# PDB2.net
KiCad netlist of a schematic drawn in EAGLE
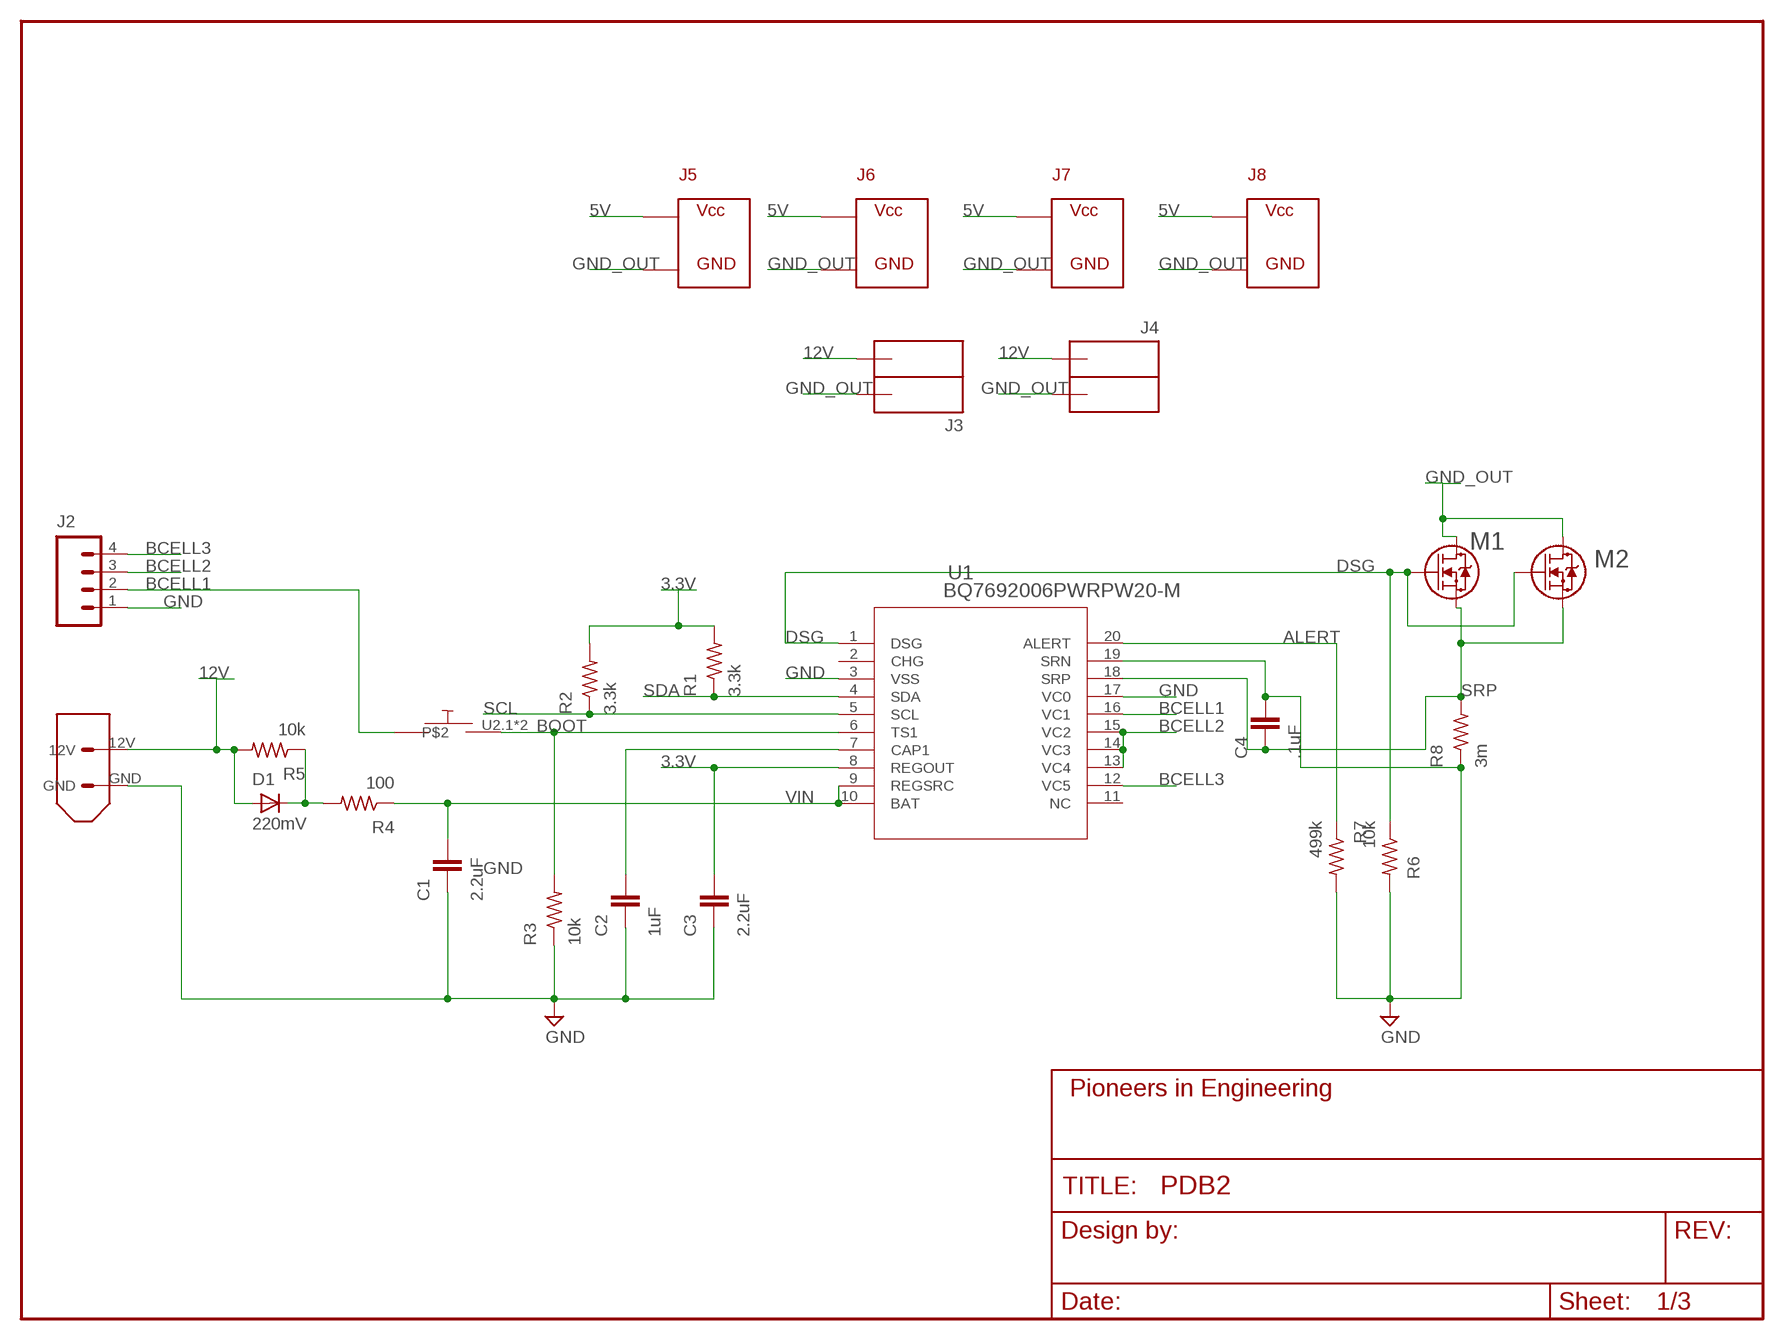
[diagram p0: schematic, sheet 1]
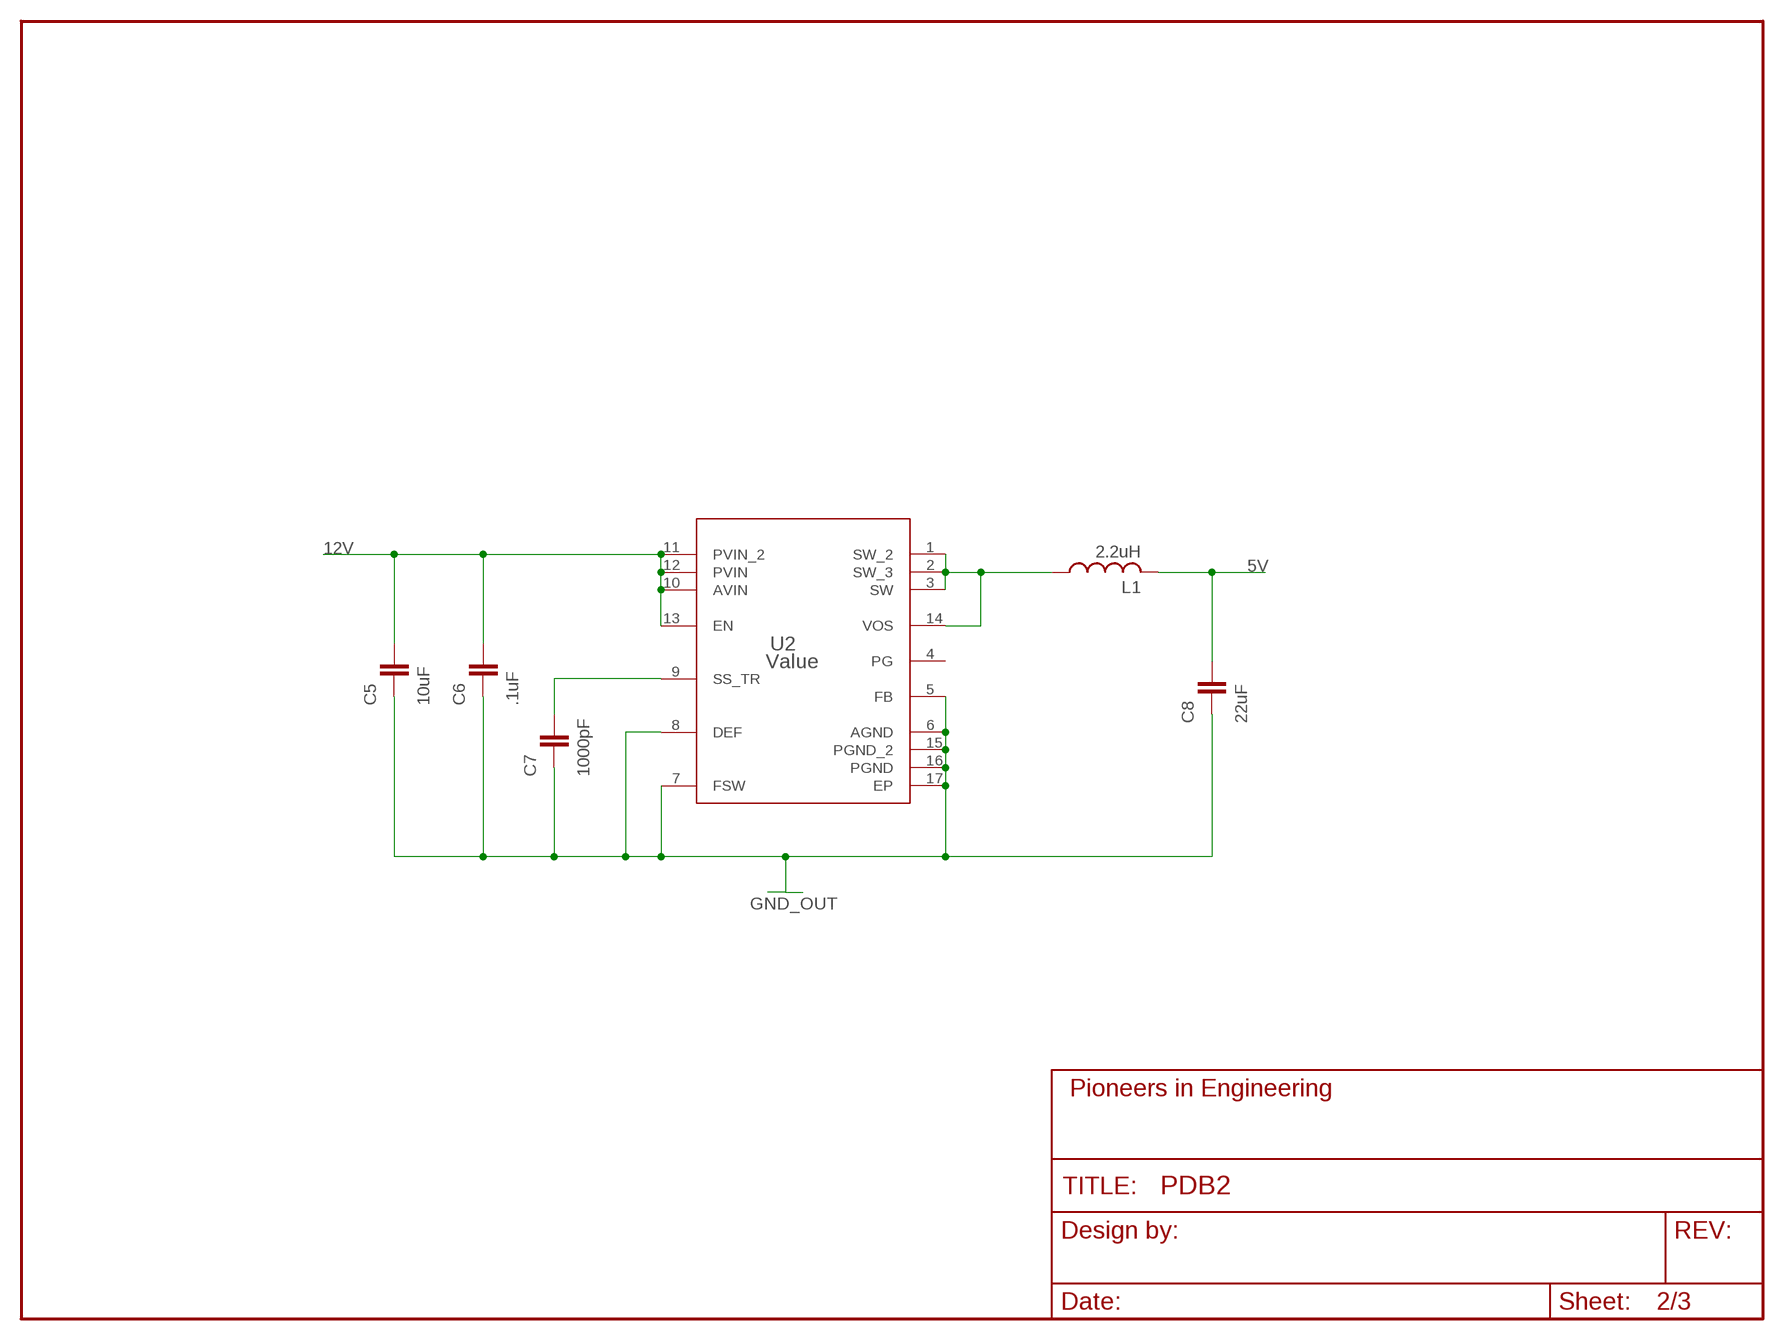
[diagram p1: schematic, sheet 2]
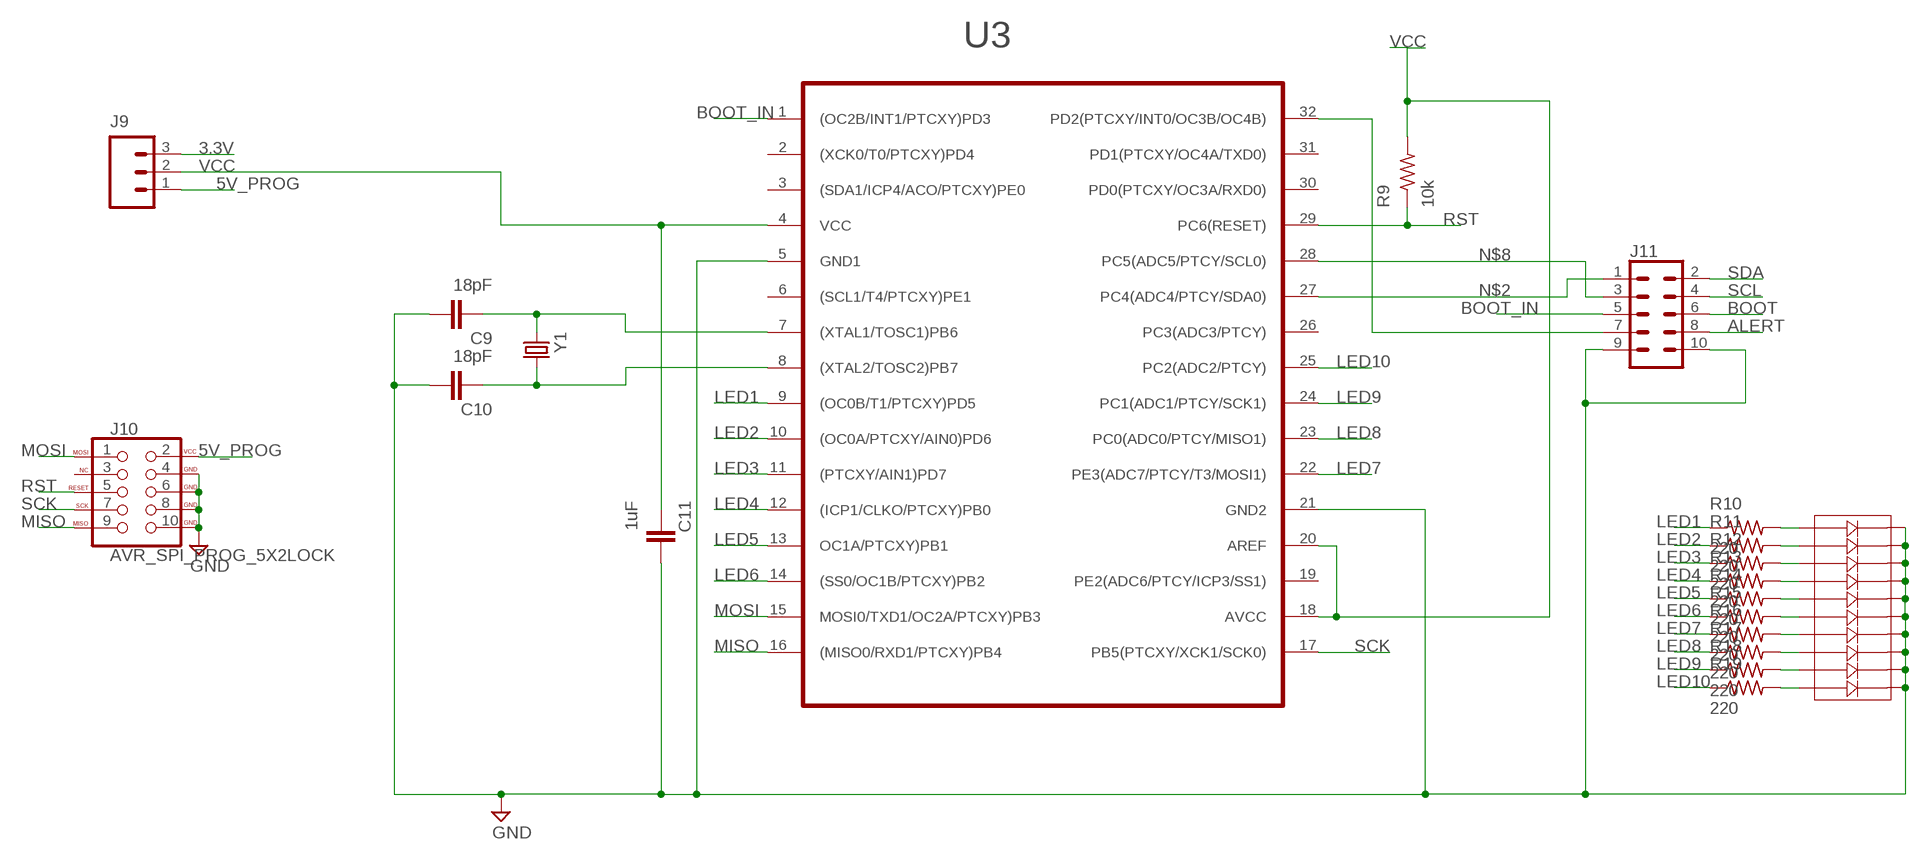
[diagram p2: schematic, sheet 3]

(export (version "E")
  (design (tool "Eeschema 10.0.6"))
  (components
    (comp (ref "C9")
      (value "18pF")
      (footprint "eagle-import:0603-CAP")
      (libsource (lib "eagle-import") (part "CAP0603-CAP"))
    )
    (comp (ref "C10")
      (value "18pF")
      (footprint "eagle-import:0603-CAP")
      (libsource (lib "eagle-import") (part "CAP0603-CAP"))
    )
    (comp (ref "C11")
      (value "1uF")
      (footprint "eagle-import:0603-CAP")
      (libsource (lib "eagle-import") (part "CAP0603-CAP"))
    )
    (comp (ref "J9")
      (value "M03PTH")
      (footprint "eagle-import:1X03")
      (libsource (lib "eagle-import") (part "M03PTH"))
    )
    (comp (ref "J10")
      (value "AVR_SPI_PROG_5X2LOCK")
      (footprint "eagle-import:2X5-SHROUDED_LOCK")
      (libsource (lib "eagle-import") (part "AVR_SPI_PROG_5X2LOCK"))
    )
    (comp (ref "J11")
      (value "CONN_05X2NO_SILK")
      (footprint "eagle-import:2X5_NOSILK")
      (libsource (lib "eagle-import") (part "CONN_05X2NO_SILK"))
    )
    (comp (ref "LED1")
      (value "BAR_SEGMENT_DISPLAY")
      (footprint "eagle-import:BAR_SEGMENT_DISPLAY")
      (libsource (lib "eagle-import") (part "BAR_SEGMENT_DISPLAY"))
    )
    (comp (ref "R9")
      (value "10k")
      (footprint "eagle-import:R0603")
      (fields (field (name "MANUFACTURER") "Rohm Semiconductor"))
      (libsource (lib "eagle-import") (part "R-US_R0603"))
    )
    (comp (ref "R10")
      (value "220")
      (footprint "eagle-import:R0603")
      (fields (field (name "MANUFACTURER") "Rohm Semiconductor"))
      (libsource (lib "eagle-import") (part "R-US_R0603"))
    )
    (comp (ref "R11")
      (value "220")
      (footprint "eagle-import:R0603")
      (fields (field (name "MANUFACTURER") "Rohm Semiconductor"))
      (libsource (lib "eagle-import") (part "R-US_R0603"))
    )
    (comp (ref "R12")
      (value "220")
      (footprint "eagle-import:R0603")
      (fields (field (name "MANUFACTURER") "Rohm Semiconductor"))
      (libsource (lib "eagle-import") (part "R-US_R0603"))
    )
    (comp (ref "R13")
      (value "220")
      (footprint "eagle-import:R0603")
      (fields (field (name "MANUFACTURER") "Rohm Semiconductor"))
      (libsource (lib "eagle-import") (part "R-US_R0603"))
    )
    (comp (ref "R14")
      (value "220")
      (footprint "eagle-import:R0603")
      (fields (field (name "MANUFACTURER") "Rohm Semiconductor"))
      (libsource (lib "eagle-import") (part "R-US_R0603"))
    )
    (comp (ref "R15")
      (value "220")
      (footprint "eagle-import:R0603")
      (fields (field (name "MANUFACTURER") "Rohm Semiconductor"))
      (libsource (lib "eagle-import") (part "R-US_R0603"))
    )
    (comp (ref "R16")
      (value "220")
      (footprint "eagle-import:R0603")
      (fields (field (name "MANUFACTURER") "Rohm Semiconductor"))
      (libsource (lib "eagle-import") (part "R-US_R0603"))
    )
    (comp (ref "R17")
      (value "220")
      (footprint "eagle-import:R0603")
      (fields (field (name "MANUFACTURER") "Rohm Semiconductor"))
      (libsource (lib "eagle-import") (part "R-US_R0603"))
    )
    (comp (ref "R18")
      (value "220")
      (footprint "eagle-import:R0603")
      (fields (field (name "MANUFACTURER") "Rohm Semiconductor"))
      (libsource (lib "eagle-import") (part "R-US_R0603"))
    )
    (comp (ref "R19")
      (value "220")
      (footprint "eagle-import:R0603")
      (fields (field (name "MANUFACTURER") "Rohm Semiconductor"))
      (libsource (lib "eagle-import") (part "R-US_R0603"))
    )
    (comp (ref "U3")
      (value "ATMEGA328PB-AU")
      (footprint "eagle-import:TQFP32-08")
      (libsource (lib "eagle-import") (part "ATMEGA328PB-AU"))
    )
    (comp (ref "Y1")
      (value "CRYSTALSMD")
      (footprint "eagle-import:HC49UP")
      (fields (field (name "PARTNO") "ABLS-8.000MHZ-B4-T"))
      (libsource (lib "eagle-import") (part "CRYSTALSMD"))
    )
    (comp (ref "BUT1")
      (value "D6C90F1LFS")
      (footprint "eagle-import:D6C_BUTTON")
      (libsource (lib "eagle-import") (part "D6C90F1LFS"))
    )
    (comp (ref "C1")
      (value "2.2uF")
      (footprint "eagle-import:0603-CAP")
      (libsource (lib "eagle-import") (part "CAP0603-CAP"))
    )
    (comp (ref "C2")
      (value "1uF")
      (footprint "eagle-import:0603-CAP")
      (libsource (lib "eagle-import") (part "CAP0603-CAP"))
    )
    (comp (ref "C3")
      (value "2.2uF")
      (footprint "eagle-import:0603-CAP")
      (libsource (lib "eagle-import") (part "CAP0603-CAP"))
    )
    (comp (ref "C4")
      (value ".1uF")
      (footprint "eagle-import:0603-CAP")
      (libsource (lib "eagle-import") (part "CAP0603-CAP"))
    )
    (comp (ref "D1")
      (value "220mV")
      (footprint "eagle-import:SOD-323")
      (libsource (lib "eagle-import") (part "DIODESOD-323"))
    )
    (comp (ref "J1")
      (value "XT60CONNECTOR")
      (footprint "eagle-import:XT60CONNECTOR")
      (fields (field (name "PARTNUMBER") "PRT-10474 "))
      (libsource (lib "eagle-import") (part "XT60CONNECTOR"))
    )
    (comp (ref "J2")
      (value "M041X04-MTA")
      (footprint "eagle-import:1X04-MTA")
      (libsource (lib "eagle-import") (part "M041X04-MTA"))
    )
    (comp (ref "J3")
      (value "ANDERSONVERTICAL")
      (footprint "eagle-import:ANDERSON_VERTICAL")
      (libsource (lib "eagle-import") (part "ANDERSONVERTICAL"))
    )
    (comp (ref "J4")
      (value "ANDERSONVERTICAL")
      (footprint "eagle-import:ANDERSON_VERTICAL")
      (libsource (lib "eagle-import") (part "ANDERSONVERTICAL"))
    )
    (comp (ref "J5")
      (value "ATX")
      (footprint "eagle-import:ATX")
      (libsource (lib "eagle-import") (part "ATX"))
    )
    (comp (ref "J6")
      (value "ATX")
      (footprint "eagle-import:ATX")
      (libsource (lib "eagle-import") (part "ATX"))
    )
    (comp (ref "J7")
      (value "ATX")
      (footprint "eagle-import:ATX")
      (libsource (lib "eagle-import") (part "ATX"))
    )
    (comp (ref "J8")
      (value "ATX")
      (footprint "eagle-import:ATX")
      (libsource (lib "eagle-import") (part "ATX"))
    )
    (comp (ref "M1")
      (value "STD20NF06LDPAK-M")
      (footprint "eagle-import:DPAK-M")
      (fields (field (name "MANUFACTURER_PART_NUMBER") "STD20NF06L"))
      (libsource (lib "eagle-import") (part "STD20NF06LDPAK-M"))
    )
    (comp (ref "M2")
      (value "STD20NF06LDPAK-M")
      (footprint "eagle-import:DPAK-M")
      (fields (field (name "MANUFACTURER_PART_NUMBER") "STD20NF06L"))
      (libsource (lib "eagle-import") (part "STD20NF06LDPAK-M"))
    )
    (comp (ref "R1")
      (value "3.3k")
      (footprint "eagle-import:R0603")
      (fields (field (name "MANUFACTURER") "Rohm Semiconductor"))
      (libsource (lib "eagle-import") (part "R-US_R0603"))
    )
    (comp (ref "R2")
      (value "3.3k")
      (footprint "eagle-import:R0603")
      (fields (field (name "MANUFACTURER") "Rohm Semiconductor"))
      (libsource (lib "eagle-import") (part "R-US_R0603"))
    )
    (comp (ref "R3")
      (value "10k")
      (footprint "eagle-import:R0603")
      (fields (field (name "MANUFACTURER") "Rohm Semiconductor"))
      (libsource (lib "eagle-import") (part "R-US_R0603"))
    )
    (comp (ref "R4")
      (value "100")
      (footprint "eagle-import:R0603")
      (fields (field (name "MANUFACTURER") "Rohm Semiconductor"))
      (libsource (lib "eagle-import") (part "R-US_R0603"))
    )
    (comp (ref "R5")
      (value "10k")
      (footprint "eagle-import:R0603")
      (fields (field (name "MANUFACTURER") "Rohm Semiconductor"))
      (libsource (lib "eagle-import") (part "R-US_R0603"))
    )
    (comp (ref "R6")
      (value "10k")
      (footprint "eagle-import:R0603")
      (fields (field (name "MANUFACTURER") "Rohm Semiconductor"))
      (libsource (lib "eagle-import") (part "R-US_R0603"))
    )
    (comp (ref "R7")
      (value "499k")
      (footprint "eagle-import:R0603")
      (fields (field (name "MANUFACTURER") "Rohm Semiconductor"))
      (libsource (lib "eagle-import") (part "R-US_R0603"))
    )
    (comp (ref "R8")
      (value "3m")
      (footprint "eagle-import:R2512")
      (libsource (lib "eagle-import") (part "R-US_R2512"))
    )
    (comp (ref "U1")
      (value "BQ7692006PWRPW20-M")
      (footprint "eagle-import:PW20-M")
      (fields (field (name "MANUFACTURER_PART_NUMBER") "BQ7692006PWR"))
      (libsource (lib "eagle-import") (part "BQ7692006PWRPW20-M"))
    )
    (comp (ref "C5")
      (value "10uF")
      (footprint "eagle-import:0603-CAP")
      (libsource (lib "eagle-import") (part "CAP0603-CAP"))
    )
    (comp (ref "C6")
      (value ".1uF")
      (footprint "eagle-import:0603-CAP")
      (libsource (lib "eagle-import") (part "CAP0603-CAP"))
    )
    (comp (ref "C7")
      (value "1000pF")
      (footprint "eagle-import:0603-CAP")
      (libsource (lib "eagle-import") (part "CAP0603-CAP"))
    )
    (comp (ref "C8")
      (value "22uF")
      (footprint "eagle-import:0603-CAP")
      (libsource (lib "eagle-import") (part "CAP0603-CAP"))
    )
    (comp (ref "L1")
      (value "2.2uH")
      (footprint "eagle-import:ASPI")
      (libsource (lib "eagle-import") (part "ASPI-0530_INDUCTOR"))
    )
    (comp (ref "U2")
      (value "Value")
      (footprint "eagle-import:RGT0016C")
      (fields
        (field (name "MANUFACTURER") "Texas Instruments")
        (field (name "MANUFACTURER_PART_NUMBER") "TPS62133RGTR")
      )
      (libsource (lib "eagle-import") (part "TPS62133RGTR"))
    )
  )
  (nets
    (net (code "1") (name "3.3V") (class "Default")
      (node (ref "C3") (pin "2") (pinfunction "2_2") (pintype "passive"))
      (node (ref "J9") (pin "3") (pinfunction "3_3") (pintype "passive"))
      (node (ref "R1") (pin "2") (pinfunction "2_2") (pintype "passive"))
      (node (ref "R2") (pin "2") (pinfunction "2_2") (pintype "passive"))
      (node (ref "U1") (pin "8") (pinfunction "REGOUT_8") (pintype "power_in"))
    )
    (net (code "2") (name "5V") (class "Default")
      (node (ref "C8") (pin "2") (pinfunction "2_2") (pintype "passive"))
      (node (ref "J5") (pin "P$1") (pinfunction "P$1_P$1") (pintype "power_in"))
      (node (ref "J6") (pin "P$1") (pinfunction "P$1_P$1") (pintype "power_in"))
      (node (ref "J7") (pin "P$1") (pinfunction "P$1_P$1") (pintype "power_in"))
      (node (ref "J8") (pin "P$1") (pinfunction "P$1_P$1") (pintype "power_in"))
      (node (ref "L1") (pin "P$2") (pinfunction "2_P$2") (pintype "passive"))
    )
    (net (code "3") (name "5V_PROG") (class "Default")
      (node (ref "J10") (pin "2") (pinfunction "VCC_2") (pintype "power_in"))
      (node (ref "J9") (pin "1") (pinfunction "1_1") (pintype "passive"))
    )
    (net (code "4") (name "12V") (class "Default")
      (node (ref "C5") (pin "2") (pinfunction "2_2") (pintype "passive"))
      (node (ref "C6") (pin "2") (pinfunction "2_2") (pintype "passive"))
      (node (ref "D1") (pin "1") (pinfunction "A_1") (pintype "passive"))
      (node (ref "J1") (pin "12V") (pinfunction "12V_12V") (pintype "bidirectional"))
      (node (ref "J3") (pin "PIN1") (pinfunction "OUTB_PIN1") (pintype "bidirectional"))
      (node (ref "J4") (pin "PIN2") (pinfunction "OUTA_PIN2") (pintype "bidirectional"))
      (node (ref "R5") (pin "2") (pinfunction "2_2") (pintype "passive"))
      (node (ref "U2") (pin "10") (pinfunction "AVIN_10") (pintype "power_in"))
      (node (ref "U2") (pin "11") (pinfunction "PVIN_2_11") (pintype "power_in"))
      (node (ref "U2") (pin "12") (pinfunction "PVIN_12") (pintype "power_in"))
      (node (ref "U2") (pin "13") (pinfunction "EN_13") (pintype "input"))
    )
    (net (code "5") (name "ALERT") (class "Default")
      (node (ref "J11") (pin "8") (pinfunction "8_8") (pintype "passive"))
      (node (ref "R7") (pin "1") (pinfunction "1_1") (pintype "passive"))
      (node (ref "U1") (pin "20") (pinfunction "ALERT_20") (pintype "bidirectional"))
    )
    (net (code "6") (name "BCELL1") (class "Default")
      (node (ref "BUT1") (pin "U1.1") (pinfunction "P$1_U1.1") (pintype "bidirectional"))
      (node (ref "BUT1") (pin "U1.2") (pinfunction "P$1_U1.2") (pintype "bidirectional"))
      (node (ref "J2") (pin "2") (pinfunction "2_2") (pintype "passive"))
      (node (ref "U1") (pin "16") (pinfunction "VC1_16") (pintype "input"))
    )
    (net (code "7") (name "BCELL2") (class "Default")
      (node (ref "J2") (pin "3") (pinfunction "3_3") (pintype "passive"))
      (node (ref "U1") (pin "13") (pinfunction "VC4_13") (pintype "input"))
      (node (ref "U1") (pin "14") (pinfunction "VC3_14") (pintype "input"))
      (node (ref "U1") (pin "15") (pinfunction "VC2_15") (pintype "input"))
    )
    (net (code "8") (name "BCELL3") (class "Default")
      (node (ref "J2") (pin "4") (pinfunction "4_4") (pintype "passive"))
      (node (ref "U1") (pin "12") (pinfunction "VC5_12") (pintype "input"))
    )
    (net (code "9") (name "BOOT") (class "Default")
      (node (ref "BUT1") (pin "U2.1") (pinfunction "P$2_U2.1") (pintype "bidirectional"))
      (node (ref "BUT1") (pin "U2.2") (pinfunction "P$2_U2.2") (pintype "bidirectional"))
      (node (ref "J11") (pin "6") (pinfunction "6_6") (pintype "passive"))
      (node (ref "R3") (pin "2") (pinfunction "2_2") (pintype "passive"))
      (node (ref "U1") (pin "6") (pinfunction "TS1_6") (pintype "input"))
    )
    (net (code "10") (name "BOOT_IN") (class "Default")
      (node (ref "J11") (pin "5") (pinfunction "5_5") (pintype "passive"))
      (node (ref "U3") (pin "1") (pinfunction "(OC2B/INT1/PTCXY)PD3_1") (pintype "bidirectional"))
    )
    (net (code "11") (name "DSG") (class "Default")
      (node (ref "M1") (pin "1") (pinfunction "1_1") (pintype "passive"))
      (node (ref "M2") (pin "1") (pinfunction "1_1") (pintype "passive"))
      (node (ref "R6") (pin "1") (pinfunction "1_1") (pintype "passive"))
      (node (ref "U1") (pin "1") (pinfunction "DSG_1") (pintype "output"))
    )
    (net (code "12") (name "GND") (class "Default")
      (node (ref "C1") (pin "1") (pinfunction "1_1") (pintype "passive"))
      (node (ref "C10") (pin "2") (pinfunction "2_2") (pintype "passive"))
      (node (ref "C11") (pin "2") (pinfunction "2_2") (pintype "passive"))
      (node (ref "C2") (pin "1") (pinfunction "1_1") (pintype "passive"))
      (node (ref "C3") (pin "1") (pinfunction "1_1") (pintype "passive"))
      (node (ref "C4") (pin "2") (pinfunction "2_2") (pintype "passive"))
      (node (ref "C9") (pin "2") (pinfunction "2_2") (pintype "passive"))
      (node (ref "J1") (pin "GND") (pinfunction "GND_GND") (pintype "bidirectional"))
      (node (ref "J10") (pin "10") (pinfunction "GND_10") (pintype "power_in"))
      (node (ref "J10") (pin "4") (pinfunction "GND_4") (pintype "power_in"))
      (node (ref "J10") (pin "6") (pinfunction "GND_6") (pintype "power_in"))
      (node (ref "J10") (pin "8") (pinfunction "GND_8") (pintype "power_in"))
      (node (ref "J11") (pin "10") (pinfunction "10_10") (pintype "passive"))
      (node (ref "J11") (pin "9") (pinfunction "9_9") (pintype "passive"))
      (node (ref "J2") (pin "1") (pinfunction "1_1") (pintype "passive"))
      (node (ref "LED1") (pin "BAR_DISPLAY10") (pinfunction "P11_BAR_DISPLAY10") (pintype "bidirectional"))
      (node (ref "LED1") (pin "BAR_DISPLAY11") (pinfunction "P12_BAR_DISPLAY11") (pintype "bidirectional"))
      (node (ref "LED1") (pin "BAR_DISPLAY12") (pinfunction "P13_BAR_DISPLAY12") (pintype "bidirectional"))
      (node (ref "LED1") (pin "BAR_DISPLAY13") (pinfunction "P14_BAR_DISPLAY13") (pintype "bidirectional"))
      (node (ref "LED1") (pin "BAR_DISPLAY14") (pinfunction "P15_BAR_DISPLAY14") (pintype "bidirectional"))
      (node (ref "LED1") (pin "BAR_DISPLAY15") (pinfunction "P16_BAR_DISPLAY15") (pintype "bidirectional"))
      (node (ref "LED1") (pin "BAR_DISPLAY16") (pinfunction "P17_BAR_DISPLAY16") (pintype "bidirectional"))
      (node (ref "LED1") (pin "BAR_DISPLAY17") (pinfunction "P18_BAR_DISPLAY17") (pintype "bidirectional"))
      (node (ref "LED1") (pin "BAR_DISPLAY18") (pinfunction "P19_BAR_DISPLAY18") (pintype "bidirectional"))
      (node (ref "LED1") (pin "BAR_DISPLAY19") (pinfunction "P20_BAR_DISPLAY19") (pintype "bidirectional"))
      (node (ref "R3") (pin "1") (pinfunction "1_1") (pintype "passive"))
      (node (ref "R6") (pin "2") (pinfunction "2_2") (pintype "passive"))
      (node (ref "R7") (pin "2") (pinfunction "2_2") (pintype "passive"))
      (node (ref "R8") (pin "1") (pinfunction "1_1") (pintype "passive"))
      (node (ref "U1") (pin "17") (pinfunction "VC0_17") (pintype "input"))
      (node (ref "U1") (pin "19") (pinfunction "SRN_19") (pintype "input"))
      (node (ref "U1") (pin "3") (pinfunction "VSS_3") (pintype "power_in"))
      (node (ref "U3") (pin "21") (pinfunction "GND2_21") (pintype "bidirectional"))
      (node (ref "U3") (pin "5") (pinfunction "GND1_5") (pintype "bidirectional"))
    )
    (net (code "13") (name "GND_OUT") (class "Default")
      (node (ref "C5") (pin "1") (pinfunction "1_1") (pintype "passive"))
      (node (ref "C6") (pin "1") (pinfunction "1_1") (pintype "passive"))
      (node (ref "C7") (pin "1") (pinfunction "1_1") (pintype "passive"))
      (node (ref "C8") (pin "1") (pinfunction "1_1") (pintype "passive"))
      (node (ref "J3") (pin "PIN2") (pinfunction "OUTA_PIN2") (pintype "bidirectional"))
      (node (ref "J4") (pin "PIN1") (pinfunction "OUTB_PIN1") (pintype "bidirectional"))
      (node (ref "J5") (pin "P$2") (pinfunction "P$2_P$2") (pintype "power_in"))
      (node (ref "J6") (pin "P$2") (pinfunction "P$2_P$2") (pintype "power_in"))
      (node (ref "J7") (pin "P$2") (pinfunction "P$2_P$2") (pintype "power_in"))
      (node (ref "J8") (pin "P$2") (pinfunction "P$2_P$2") (pintype "power_in"))
      (node (ref "M1") (pin "3") (pinfunction "2_3") (pintype "passive"))
      (node (ref "M2") (pin "3") (pinfunction "2_3") (pintype "passive"))
      (node (ref "U2") (pin "15") (pinfunction "PGND_2_15") (pintype "power_in"))
      (node (ref "U2") (pin "16") (pinfunction "PGND_16") (pintype "power_in"))
      (node (ref "U2") (pin "17") (pinfunction "EP_17") (pintype "power_in"))
      (node (ref "U2") (pin "5") (pinfunction "FB_5") (pintype "input"))
      (node (ref "U2") (pin "6") (pinfunction "AGND_6") (pintype "power_in"))
      (node (ref "U2") (pin "7") (pinfunction "FSW_7") (pintype "input"))
      (node (ref "U2") (pin "8") (pinfunction "DEF_8") (pintype "input"))
    )
    (net (code "14") (name "LED1") (class "Default")
      (node (ref "R10") (pin "1") (pinfunction "1_1") (pintype "passive"))
      (node (ref "U3") (pin "9") (pinfunction "(OC0B/T1/PTCXY)PD5_9") (pintype "bidirectional"))
    )
    (net (code "15") (name "LED2") (class "Default")
      (node (ref "R11") (pin "1") (pinfunction "1_1") (pintype "passive"))
      (node (ref "U3") (pin "10") (pinfunction "(OC0A/PTCXY/AIN0)PD6_10") (pintype "bidirectional"))
    )
    (net (code "16") (name "LED3") (class "Default")
      (node (ref "R12") (pin "1") (pinfunction "1_1") (pintype "passive"))
      (node (ref "U3") (pin "11") (pinfunction "(PTCXY/AIN1)PD7_11") (pintype "bidirectional"))
    )
    (net (code "17") (name "LED4") (class "Default")
      (node (ref "R13") (pin "1") (pinfunction "1_1") (pintype "passive"))
      (node (ref "U3") (pin "12") (pinfunction "(ICP1/CLKO/PTCXY)PB0_12") (pintype "bidirectional"))
    )
    (net (code "18") (name "LED5") (class "Default")
      (node (ref "R14") (pin "1") (pinfunction "1_1") (pintype "passive"))
      (node (ref "U3") (pin "13") (pinfunction "OC1A/PTCXY)PB1_13") (pintype "bidirectional"))
    )
    (net (code "19") (name "LED6") (class "Default")
      (node (ref "R15") (pin "1") (pinfunction "1_1") (pintype "passive"))
      (node (ref "U3") (pin "14") (pinfunction "(SS0/OC1B/PTCXY)PB2_14") (pintype "bidirectional"))
    )
    (net (code "20") (name "LED7") (class "Default")
      (node (ref "R16") (pin "1") (pinfunction "1_1") (pintype "passive"))
      (node (ref "U3") (pin "22") (pinfunction "PE3(ADC7/PTCY/T3/MOSI1)_22") (pintype "bidirectional"))
    )
    (net (code "21") (name "LED8") (class "Default")
      (node (ref "R17") (pin "1") (pinfunction "1_1") (pintype "passive"))
      (node (ref "U3") (pin "23") (pinfunction "PC0(ADC0/PTCY/MISO1)_23") (pintype "bidirectional"))
    )
    (net (code "22") (name "LED9") (class "Default")
      (node (ref "R18") (pin "1") (pinfunction "1_1") (pintype "passive"))
      (node (ref "U3") (pin "24") (pinfunction "PC1(ADC1/PTCY/SCK1)_24") (pintype "bidirectional"))
    )
    (net (code "23") (name "LED10") (class "Default")
      (node (ref "R19") (pin "1") (pinfunction "1_1") (pintype "passive"))
      (node (ref "U3") (pin "25") (pinfunction "PC2(ADC2/PTCY)_25") (pintype "bidirectional"))
    )
    (net (code "24") (name "MISO") (class "Default")
      (node (ref "J10") (pin "9") (pinfunction "MISO_9") (pintype "passive"))
      (node (ref "U3") (pin "16") (pinfunction "(MISO0/RXD1/PTCXY)PB4_16") (pintype "bidirectional"))
    )
    (net (code "25") (name "MOSI") (class "Default")
      (node (ref "J10") (pin "1") (pinfunction "MOSI_1") (pintype "passive"))
      (node (ref "U3") (pin "15") (pinfunction "MOSI0/TXD1/OC2A/PTCXY)PB3_15") (pintype "bidirectional"))
    )
    (net (code "26") (name "N$2") (class "Default")
      (node (ref "J11") (pin "1") (pinfunction "1_1") (pintype "passive"))
      (node (ref "U3") (pin "27") (pinfunction "PC4(ADC4/PTCY/SDA0)_27") (pintype "bidirectional"))
    )
    (net (code "27") (name "N$8") (class "Default")
      (node (ref "J11") (pin "3") (pinfunction "3_3") (pintype "passive"))
      (node (ref "U3") (pin "28") (pinfunction "PC5(ADC5/PTCY/SCL0)_28") (pintype "bidirectional"))
    )
    (net (code "28") (name "Net-(D1-C)") (class "Default")
      (node (ref "D1") (pin "2") (pinfunction "C_2") (pintype "passive"))
      (node (ref "R4") (pin "2") (pinfunction "2_2") (pintype "passive"))
      (node (ref "R5") (pin "1") (pinfunction "1_1") (pintype "passive"))
    )
    (net (code "29") (name "Net-(L1-1)") (class "Default")
      (node (ref "L1") (pin "P$1") (pinfunction "1_P$1") (pintype "passive"))
      (node (ref "U2") (pin "1") (pinfunction "SW_2_1") (pintype "power_in"))
      (node (ref "U2") (pin "14") (pinfunction "VOS_14") (pintype "input"))
      (node (ref "U2") (pin "2") (pinfunction "SW_3_2") (pintype "power_in"))
      (node (ref "U2") (pin "3") (pinfunction "SW_3") (pintype "power_in"))
    )
    (net (code "30") (name "Net-(LED1-P1)") (class "Default")
      (node (ref "LED1") (pin "BAR_DISPLAY0") (pinfunction "P1_BAR_DISPLAY0") (pintype "bidirectional"))
      (node (ref "R10") (pin "2") (pinfunction "2_2") (pintype "passive"))
    )
    (net (code "31") (name "Net-(LED1-P2)") (class "Default")
      (node (ref "LED1") (pin "BAR_DISPLAY1") (pinfunction "P2_BAR_DISPLAY1") (pintype "bidirectional"))
      (node (ref "R11") (pin "2") (pinfunction "2_2") (pintype "passive"))
    )
    (net (code "32") (name "Net-(LED1-P3)") (class "Default")
      (node (ref "LED1") (pin "BAR_DISPLAY2") (pinfunction "P3_BAR_DISPLAY2") (pintype "bidirectional"))
      (node (ref "R12") (pin "2") (pinfunction "2_2") (pintype "passive"))
    )
    (net (code "33") (name "Net-(LED1-P4)") (class "Default")
      (node (ref "LED1") (pin "BAR_DISPLAY3") (pinfunction "P4_BAR_DISPLAY3") (pintype "bidirectional"))
      (node (ref "R13") (pin "2") (pinfunction "2_2") (pintype "passive"))
    )
    (net (code "34") (name "Net-(LED1-P5)") (class "Default")
      (node (ref "LED1") (pin "BAR_DISPLAY4") (pinfunction "P5_BAR_DISPLAY4") (pintype "bidirectional"))
      (node (ref "R14") (pin "2") (pinfunction "2_2") (pintype "passive"))
    )
    (net (code "35") (name "Net-(LED1-P6)") (class "Default")
      (node (ref "LED1") (pin "BAR_DISPLAY5") (pinfunction "P6_BAR_DISPLAY5") (pintype "bidirectional"))
      (node (ref "R15") (pin "2") (pinfunction "2_2") (pintype "passive"))
    )
    (net (code "36") (name "Net-(LED1-P7)") (class "Default")
      (node (ref "LED1") (pin "BAR_DISPLAY6") (pinfunction "P7_BAR_DISPLAY6") (pintype "bidirectional"))
      (node (ref "R16") (pin "2") (pinfunction "2_2") (pintype "passive"))
    )
    (net (code "37") (name "Net-(LED1-P8)") (class "Default")
      (node (ref "LED1") (pin "BAR_DISPLAY7") (pinfunction "P8_BAR_DISPLAY7") (pintype "bidirectional"))
      (node (ref "R17") (pin "2") (pinfunction "2_2") (pintype "passive"))
    )
    (net (code "38") (name "Net-(LED1-P9)") (class "Default")
      (node (ref "LED1") (pin "BAR_DISPLAY8") (pinfunction "P9_BAR_DISPLAY8") (pintype "bidirectional"))
      (node (ref "R18") (pin "2") (pinfunction "2_2") (pintype "passive"))
    )
    (net (code "39") (name "Net-(LED1-P10)") (class "Default")
      (node (ref "LED1") (pin "BAR_DISPLAY9") (pinfunction "P10_BAR_DISPLAY9") (pintype "bidirectional"))
      (node (ref "R19") (pin "2") (pinfunction "2_2") (pintype "passive"))
    )
    (net (code "40") (name "Net-(U1-CAP1)") (class "Default")
      (node (ref "C2") (pin "2") (pinfunction "2_2") (pintype "passive"))
      (node (ref "U1") (pin "7") (pinfunction "CAP1_7") (pintype "output"))
    )
    (net (code "41") (name "Net-(U2-SS_TR)") (class "Default")
      (node (ref "C7") (pin "2") (pinfunction "2_2") (pintype "passive"))
      (node (ref "U2") (pin "9") (pinfunction "SS_TR_9") (pintype "input"))
    )
    (net (code "42") (name "Net-(U3-(XTAL1{slash}TOSC1)PB6)") (class "Default")
      (node (ref "C9") (pin "1") (pinfunction "1_1") (pintype "passive"))
      (node (ref "U3") (pin "7") (pinfunction "(XTAL1/TOSC1)PB6_7") (pintype "bidirectional"))
      (node (ref "Y1") (pin "1") (pinfunction "1_1") (pintype "passive"))
    )
    (net (code "43") (name "Net-(U3-(XTAL2{slash}TOSC2)PB7)") (class "Default")
      (node (ref "C10") (pin "1") (pinfunction "1_1") (pintype "passive"))
      (node (ref "U3") (pin "8") (pinfunction "(XTAL2/TOSC2)PB7_8") (pintype "bidirectional"))
      (node (ref "Y1") (pin "2") (pinfunction "2_2") (pintype "passive"))
    )
    (net (code "44") (name "Net-(U3-PD2(PTCXY{slash}INT0{slash}OC3B{slash}OC4B))") (class "Default")
      (node (ref "J11") (pin "7") (pinfunction "7_7") (pintype "passive"))
      (node (ref "U3") (pin "32") (pinfunction "PD2(PTCXY/INT0/OC3B/OC4B)_32") (pintype "bidirectional"))
    )
    (net (code "45") (name "RST") (class "Default")
      (node (ref "J10") (pin "5") (pinfunction "RESET_5") (pintype "passive"))
      (node (ref "R9") (pin "1") (pinfunction "1_1") (pintype "passive"))
      (node (ref "U3") (pin "29") (pinfunction "PC6(RESET)_29") (pintype "bidirectional"))
    )
    (net (code "46") (name "SCK") (class "Default")
      (node (ref "J10") (pin "7") (pinfunction "SCK_7") (pintype "passive"))
      (node (ref "U3") (pin "17") (pinfunction "PB5(PTCXY/XCK1/SCK0)_17") (pintype "bidirectional"))
    )
    (net (code "47") (name "SCL") (class "Default")
      (node (ref "J11") (pin "4") (pinfunction "4_4") (pintype "passive"))
      (node (ref "R2") (pin "1") (pinfunction "1_1") (pintype "passive"))
      (node (ref "U1") (pin "5") (pinfunction "SCL_5") (pintype "input"))
    )
    (net (code "48") (name "SDA") (class "Default")
      (node (ref "J11") (pin "2") (pinfunction "2_2") (pintype "passive"))
      (node (ref "R1") (pin "1") (pinfunction "1_1") (pintype "passive"))
      (node (ref "U1") (pin "4") (pinfunction "SDA_4") (pintype "bidirectional"))
    )
    (net (code "49") (name "SRP") (class "Default")
      (node (ref "C4") (pin "1") (pinfunction "1_1") (pintype "passive"))
      (node (ref "M1") (pin "2") (pinfunction "3_2") (pintype "passive"))
      (node (ref "M2") (pin "2") (pinfunction "3_2") (pintype "passive"))
      (node (ref "R8") (pin "2") (pinfunction "2_2") (pintype "passive"))
      (node (ref "U1") (pin "18") (pinfunction "SRP_18") (pintype "input"))
    )
    (net (code "50") (name "VCC") (class "Default")
      (node (ref "C11") (pin "1") (pinfunction "1_1") (pintype "passive"))
      (node (ref "J9") (pin "2") (pinfunction "2_2") (pintype "passive"))
      (node (ref "R9") (pin "2") (pinfunction "2_2") (pintype "passive"))
      (node (ref "U3") (pin "18") (pinfunction "AVCC_18") (pintype "bidirectional"))
      (node (ref "U3") (pin "20") (pinfunction "AREF_20") (pintype "bidirectional"))
      (node (ref "U3") (pin "4") (pinfunction "VCC_4") (pintype "bidirectional"))
    )
    (net (code "51") (name "VIN") (class "Default")
      (node (ref "C1") (pin "2") (pinfunction "2_2") (pintype "passive"))
      (node (ref "R4") (pin "1") (pinfunction "1_1") (pintype "passive"))
      (node (ref "U1") (pin "10") (pinfunction "BAT_10") (pintype "power_in"))
      (node (ref "U1") (pin "9") (pinfunction "REGSRC_9") (pintype "input"))
    )
    (net (code "52") (name "unconnected-(J10-NC-Pad3)") (class "Default")
      (node (ref "J10") (pin "3") (pinfunction "NC_3") (pintype "no_connect"))
    )
    (net (code "53") (name "unconnected-(U1-CHG-Pad2)") (class "Default")
      (node (ref "U1") (pin "2") (pinfunction "CHG_2") (pintype "output"))
    )
    (net (code "54") (name "unconnected-(U1-NC-Pad11)") (class "Default")
      (node (ref "U1") (pin "11") (pinfunction "NC_11") (pintype "no_connect"))
    )
    (net (code "55") (name "unconnected-(U2-PG-Pad4)") (class "Default")
      (node (ref "U2") (pin "4") (pinfunction "PG_4") (pintype "open_collector"))
    )
    (net (code "56") (name "unconnected-(U3-(SCL1{slash}T4{slash}PTCXY)PE1-Pad6)") (class "Default")
      (node (ref "U3") (pin "6") (pinfunction "(SCL1/T4/PTCXY)PE1_6") (pintype "bidirectional"))
    )
    (net (code "57") (name "unconnected-(U3-(SDA1{slash}ICP4{slash}ACO{slash}PTCXY)PE0-Pad3)") (class "Default")
      (node (ref "U3") (pin "3") (pinfunction "(SDA1/ICP4/ACO/PTCXY)PE0_3") (pintype "bidirectional"))
    )
    (net (code "58") (name "unconnected-(U3-(XCK0{slash}T0{slash}PTCXY)PD4-Pad2)") (class "Default")
      (node (ref "U3") (pin "2") (pinfunction "(XCK0/T0/PTCXY)PD4_2") (pintype "bidirectional"))
    )
    (net (code "59") (name "unconnected-(U3-PC3(ADC3{slash}PTCY)-Pad26)") (class "Default")
      (node (ref "U3") (pin "26") (pinfunction "PC3(ADC3/PTCY)_26") (pintype "bidirectional"))
    )
    (net (code "60") (name "unconnected-(U3-PD0(PTCXY{slash}OC3A{slash}RXD0)-Pad30)") (class "Default")
      (node (ref "U3") (pin "30") (pinfunction "PD0(PTCXY/OC3A/RXD0)_30") (pintype "bidirectional"))
    )
    (net (code "61") (name "unconnected-(U3-PD1(PTCXY{slash}OC4A{slash}TXD0)-Pad31)") (class "Default")
      (node (ref "U3") (pin "31") (pinfunction "PD1(PTCXY/OC4A/TXD0)_31") (pintype "bidirectional"))
    )
    (net (code "62") (name "unconnected-(U3-PE2(ADC6{slash}PTCY{slash}ICP3{slash}SS1)-Pad19)") (class "Default")
      (node (ref "U3") (pin "19") (pinfunction "PE2(ADC6/PTCY/ICP3/SS1)_19") (pintype "bidirectional"))
    )
  )
)
